# Wise-1510-v1_1_0.net
KiCad netlist of a schematic drawn in EAGLE
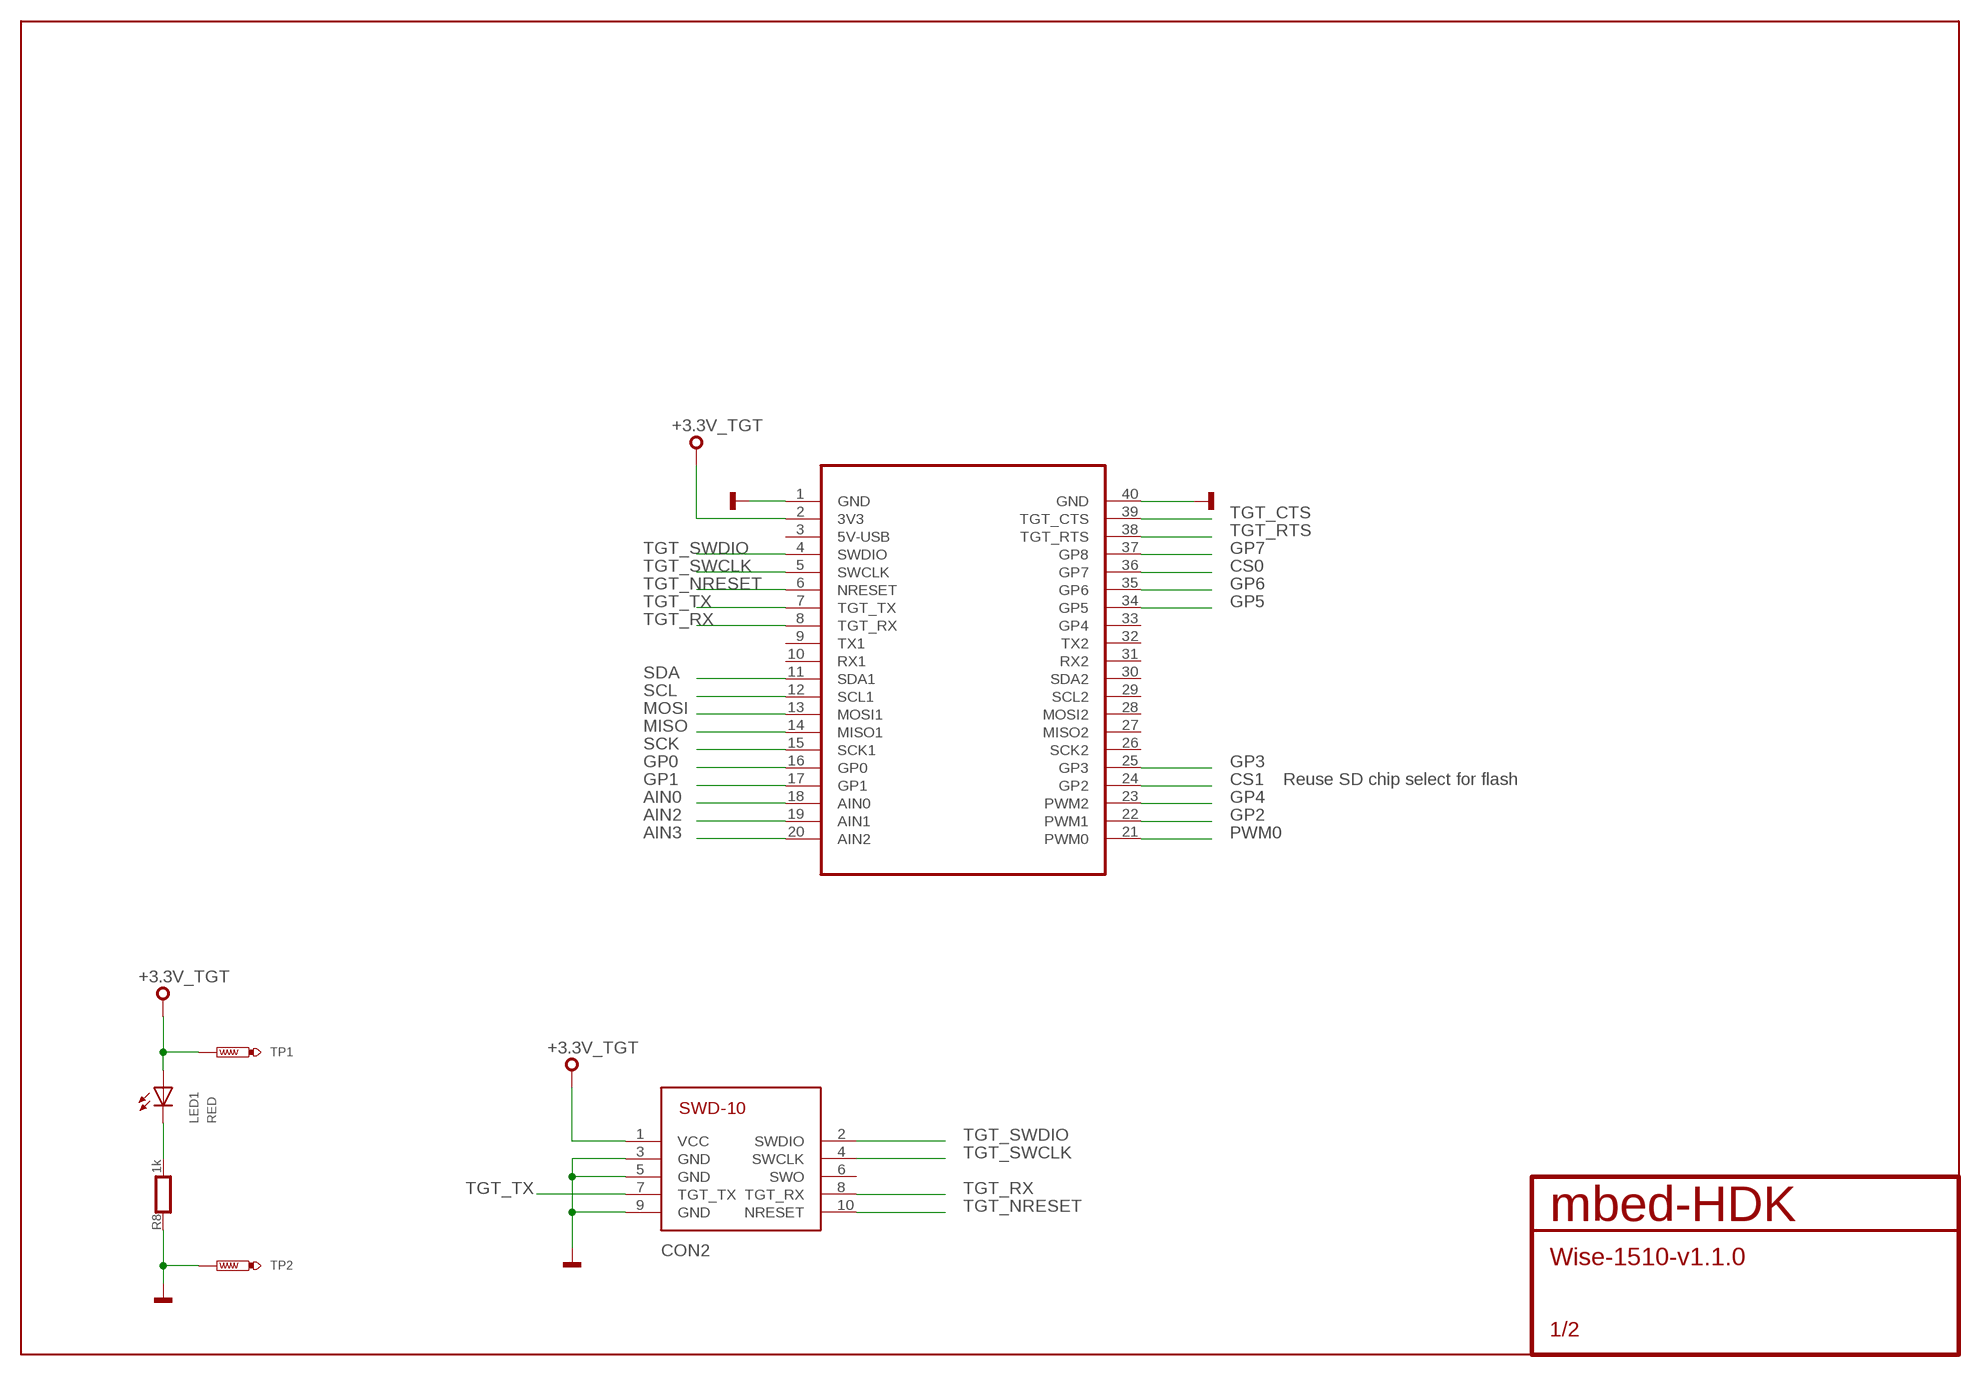
[diagram p0: schematic, sheet 1]
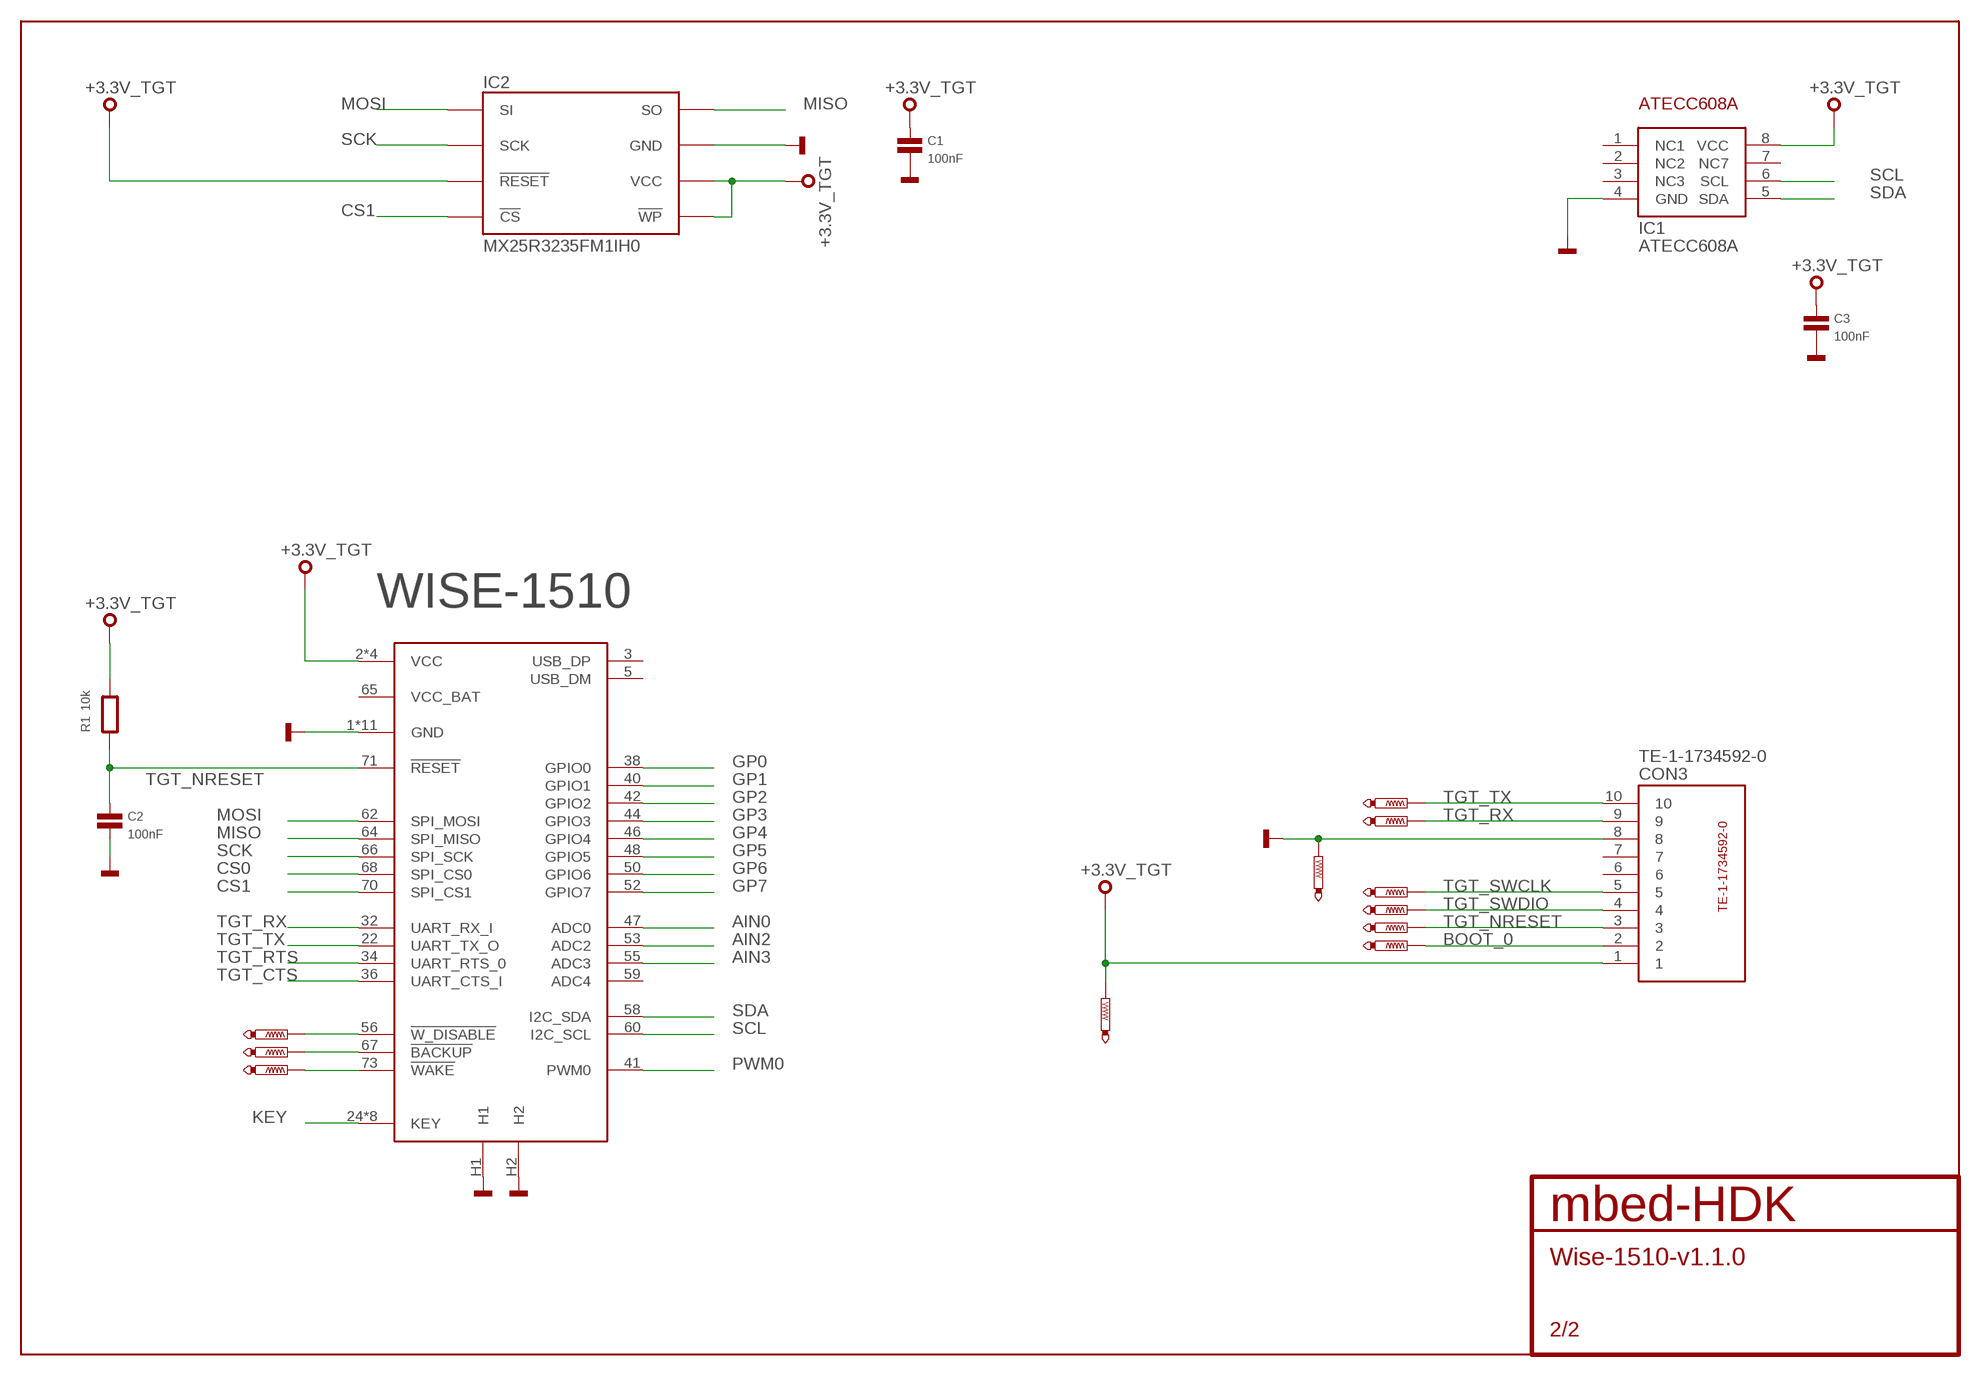
[diagram p1: schematic, sheet 2]

(export (version "E")
  (design (tool "Eeschema 10.0.6"))
  (components
    (comp (ref "C1")
      (value "100nF")
      (footprint "eagle-import:0603")
      (libsource (lib "eagle-import") (part "CAPACITOR0603"))
    )
    (comp (ref "C2")
      (value "100nF")
      (footprint "eagle-import:0603")
      (libsource (lib "eagle-import") (part "CAPACITOR0603"))
    )
    (comp (ref "C3")
      (value "100nF")
      (footprint "eagle-import:0603")
      (libsource (lib "eagle-import") (part "CAPACITOR0603"))
    )
    (comp (ref "CON1")
      (value "WISE-1510_E")
      (footprint "eagle-import:MDT420E02001")
      (libsource (lib "eagle-import") (part "WISE-1510_E"))
    )
    (comp (ref "CON3")
      (value "TE-1-1734592-0")
      (footprint "eagle-import:TE-1-1734592-0")
      (libsource (lib "eagle-import") (part "TE-1-1734592-0"))
    )
    (comp (ref "IC1")
      (value "ATECC608A")
      (footprint "eagle-import:SO8")
      (libsource (lib "eagle-import") (part "ATECC608A"))
    )
    (comp (ref "IC2")
      (value "MX25R3235FM1IH0")
      (footprint "eagle-import:SO8")
      (fields (field (name "MF") "Macronix"))
      (libsource (lib "eagle-import") (part "MX25R3235FM1IH0"))
    )
    (comp (ref "R1")
      (value "10k")
      (footprint "eagle-import:0603")
      (libsource (lib "eagle-import") (part "RESISTOR0603"))
    )
    (comp (ref "TP3")
      (value "PTR1TP08R")
      (footprint "eagle-import:TP08R")
      (libsource (lib "eagle-import") (part "PTR1TP08R"))
    )
    (comp (ref "TP4")
      (value "PTR1TP08R")
      (footprint "eagle-import:TP08R")
      (libsource (lib "eagle-import") (part "PTR1TP08R"))
    )
    (comp (ref "TP5")
      (value "PTR1TP08R")
      (footprint "eagle-import:TP08R")
      (libsource (lib "eagle-import") (part "PTR1TP08R"))
    )
    (comp (ref "TP6")
      (value "PTR1TP08R")
      (footprint "eagle-import:TP08R")
      (libsource (lib "eagle-import") (part "PTR1TP08R"))
    )
    (comp (ref "TP7")
      (value "PTR1TP08R")
      (footprint "eagle-import:TP08R")
      (libsource (lib "eagle-import") (part "PTR1TP08R"))
    )
    (comp (ref "TP8")
      (value "PTR1TP08R")
      (footprint "eagle-import:TP08R")
      (libsource (lib "eagle-import") (part "PTR1TP08R"))
    )
    (comp (ref "TP9")
      (value "PTR1B1,27")
      (footprint "eagle-import:B1,27")
      (libsource (lib "eagle-import") (part "PTR1B1,27"))
    )
    (comp (ref "TP10")
      (value "PTR1B1,27")
      (footprint "eagle-import:B1,27")
      (libsource (lib "eagle-import") (part "PTR1B1,27"))
    )
    (comp (ref "TP11")
      (value "PTR1B1,27")
      (footprint "eagle-import:B1,27")
      (libsource (lib "eagle-import") (part "PTR1B1,27"))
    )
    (comp (ref "TP12")
      (value "PTR1TP08R")
      (footprint "eagle-import:TP08R")
      (libsource (lib "eagle-import") (part "PTR1TP08R"))
    )
    (comp (ref "TP13")
      (value "PTR1TP08R")
      (footprint "eagle-import:TP08R")
      (libsource (lib "eagle-import") (part "PTR1TP08R"))
    )
    (comp (ref "CON2")
      (value "SWD-10/TC2050_SMD")
      (footprint "eagle-import:FTSH-105-02")
      (libsource (lib "eagle-import") (part "SWD-10/TC2050_SMD"))
    )
    (comp (ref "LED1")
      (value "RED")
      (footprint "eagle-import:CHIPLED_0603")
      (fields (field (name "MF") "Wurth Electronics Inc"))
      (libsource (lib "eagle-import") (part "SMD_LED0603"))
    )
    (comp (ref "R8")
      (value "1k")
      (footprint "eagle-import:0603")
      (libsource (lib "eagle-import") (part "RESISTOR0603"))
    )
    (comp (ref "TP1")
      (value "TEST-POINT-50R-PTH")
      (footprint "eagle-import:TP50-PTH")
      (libsource (lib "eagle-import") (part "TEST-POINT-50R-PTH"))
    )
    (comp (ref "TP2")
      (value "TEST-POINT-50R-PTH")
      (footprint "eagle-import:TP50-PTH")
      (libsource (lib "eagle-import") (part "TEST-POINT-50R-PTH"))
    )
    (comp (ref "U$1")
      (value "MODULE_DAUGHTER")
      (footprint "eagle-import:MODULE_DAUGHTER")
      (libsource (lib "eagle-import") (part "MODULE_DAUGHTER"))
    )
  )
  (nets
    (net (code "1") (name "+3.3V_TGT") (class "Default")
      (node (ref "C1") (pin "1") (pinfunction "P$1_1") (pintype "passive"))
      (node (ref "C3") (pin "1") (pinfunction "P$1_1") (pintype "passive"))
      (node (ref "CON1") (pin "2") (pinfunction "VCC_2") (pintype "bidirectional"))
      (node (ref "CON1") (pin "4") (pinfunction "VCC_4") (pintype "bidirectional"))
      (node (ref "CON1") (pin "72") (pinfunction "VCC_72") (pintype "bidirectional"))
      (node (ref "CON1") (pin "74") (pinfunction "VCC_74") (pintype "bidirectional"))
      (node (ref "CON2") (pin "1") (pinfunction "VCC_1") (pintype "bidirectional"))
      (node (ref "CON3") (pin "1") (pinfunction "1_1") (pintype "bidirectional"))
      (node (ref "IC1") (pin "8") (pinfunction "VCC_8") (pintype "bidirectional"))
      (node (ref "IC2") (pin "3") (pinfunction "~{WP}_3") (pintype "bidirectional"))
      (node (ref "IC2") (pin "7") (pinfunction "~{RESET}_7") (pintype "bidirectional"))
      (node (ref "IC2") (pin "8") (pinfunction "VCC_8") (pintype "bidirectional"))
      (node (ref "LED1") (pin "A") (pinfunction "A_A") (pintype "passive"))
      (node (ref "R1") (pin "2") (pinfunction "P$2_2") (pintype "passive"))
      (node (ref "TP1") (pin "TP") (pinfunction "TP_TP") (pintype "input"))
      (node (ref "TP12") (pin "TP") (pinfunction "TP_TP") (pintype "input"))
      (node (ref "U$1") (pin "2") (pinfunction "3V3_2") (pintype "bidirectional"))
    )
    (net (code "2") (name "AIN0") (class "Default")
      (node (ref "CON1") (pin "47") (pinfunction "ADC0_47") (pintype "bidirectional"))
      (node (ref "U$1") (pin "18") (pinfunction "AIN0_18") (pintype "bidirectional"))
    )
    (net (code "3") (name "AIN2") (class "Default")
      (node (ref "CON1") (pin "53") (pinfunction "ADC2_53") (pintype "bidirectional"))
      (node (ref "U$1") (pin "19") (pinfunction "AIN1_19") (pintype "bidirectional"))
    )
    (net (code "4") (name "AIN3") (class "Default")
      (node (ref "CON1") (pin "55") (pinfunction "ADC3_55") (pintype "bidirectional"))
      (node (ref "U$1") (pin "20") (pinfunction "AIN2_20") (pintype "bidirectional"))
    )
    (net (code "5") (name "BOOT_0") (class "Default")
      (node (ref "CON3") (pin "2") (pinfunction "2_2") (pintype "bidirectional"))
      (node (ref "TP8") (pin "TP") (pinfunction "TP_TP") (pintype "input"))
    )
    (net (code "6") (name "CS0") (class "Default")
      (node (ref "CON1") (pin "68") (pinfunction "SPI_CS0_68") (pintype "bidirectional"))
      (node (ref "U$1") (pin "36") (pinfunction "GP7_36") (pintype "bidirectional"))
    )
    (net (code "7") (name "CS1") (class "Default")
      (node (ref "CON1") (pin "70") (pinfunction "SPI_CS1_70") (pintype "bidirectional"))
      (node (ref "IC2") (pin "1") (pinfunction "~{CS}_1") (pintype "bidirectional"))
      (node (ref "U$1") (pin "24") (pinfunction "GP2_24") (pintype "bidirectional"))
    )
    (net (code "8") (name "GND") (class "Default")
      (node (ref "C1") (pin "2") (pinfunction "P$2_2") (pintype "passive"))
      (node (ref "C2") (pin "2") (pinfunction "P$2_2") (pintype "passive"))
      (node (ref "C3") (pin "2") (pinfunction "P$2_2") (pintype "passive"))
      (node (ref "CON1") (pin "1") (pinfunction "GND_1") (pintype "bidirectional"))
      (node (ref "CON1") (pin "18") (pinfunction "GND_18") (pintype "bidirectional"))
      (node (ref "CON1") (pin "33") (pinfunction "GND_33") (pintype "bidirectional"))
      (node (ref "CON1") (pin "39") (pinfunction "GND_39") (pintype "bidirectional"))
      (node (ref "CON1") (pin "45") (pinfunction "GND_45") (pintype "bidirectional"))
      (node (ref "CON1") (pin "51") (pinfunction "GND_51") (pintype "bidirectional"))
      (node (ref "CON1") (pin "57") (pinfunction "GND_57") (pintype "bidirectional"))
      (node (ref "CON1") (pin "63") (pinfunction "GND_63") (pintype "bidirectional"))
      (node (ref "CON1") (pin "69") (pinfunction "GND_69") (pintype "bidirectional"))
      (node (ref "CON1") (pin "7") (pinfunction "GND_7") (pintype "bidirectional"))
      (node (ref "CON1") (pin "75") (pinfunction "GND_75") (pintype "bidirectional"))
      (node (ref "CON1") (pin "H1") (pinfunction "H1_H1") (pintype "bidirectional"))
      (node (ref "CON1") (pin "H2") (pinfunction "H2_H2") (pintype "bidirectional"))
      (node (ref "CON2") (pin "3") (pinfunction "GND_3") (pintype "bidirectional"))
      (node (ref "CON2") (pin "5") (pinfunction "GND_5") (pintype "bidirectional"))
      (node (ref "CON2") (pin "9") (pinfunction "GND_9") (pintype "bidirectional"))
      (node (ref "CON3") (pin "8") (pinfunction "8_8") (pintype "bidirectional"))
      (node (ref "IC1") (pin "4") (pinfunction "GND_4") (pintype "bidirectional"))
      (node (ref "IC2") (pin "4") (pinfunction "GND_4") (pintype "bidirectional"))
      (node (ref "R8") (pin "1") (pinfunction "P$1_1") (pintype "passive"))
      (node (ref "TP13") (pin "TP") (pinfunction "TP_TP") (pintype "input"))
      (node (ref "TP2") (pin "TP") (pinfunction "TP_TP") (pintype "input"))
      (node (ref "U$1") (pin "1") (pinfunction "GND_1") (pintype "bidirectional"))
      (node (ref "U$1") (pin "40") (pinfunction "GND_40") (pintype "bidirectional"))
    )
    (net (code "9") (name "GP0") (class "Default")
      (node (ref "CON1") (pin "38") (pinfunction "GPIO0_38") (pintype "bidirectional"))
      (node (ref "U$1") (pin "16") (pinfunction "GP0_16") (pintype "bidirectional"))
    )
    (net (code "10") (name "GP1") (class "Default")
      (node (ref "CON1") (pin "40") (pinfunction "GPIO1_40") (pintype "bidirectional"))
      (node (ref "U$1") (pin "17") (pinfunction "GP1_17") (pintype "bidirectional"))
    )
    (net (code "11") (name "GP2") (class "Default")
      (node (ref "CON1") (pin "42") (pinfunction "GPIO2_42") (pintype "bidirectional"))
      (node (ref "U$1") (pin "22") (pinfunction "PWM1_22") (pintype "bidirectional"))
    )
    (net (code "12") (name "GP3") (class "Default")
      (node (ref "CON1") (pin "44") (pinfunction "GPIO3_44") (pintype "bidirectional"))
      (node (ref "U$1") (pin "25") (pinfunction "GP3_25") (pintype "bidirectional"))
    )
    (net (code "13") (name "GP4") (class "Default")
      (node (ref "CON1") (pin "46") (pinfunction "GPIO4_46") (pintype "bidirectional"))
      (node (ref "U$1") (pin "23") (pinfunction "PWM2_23") (pintype "bidirectional"))
    )
    (net (code "14") (name "GP5") (class "Default")
      (node (ref "CON1") (pin "48") (pinfunction "GPIO5_48") (pintype "bidirectional"))
      (node (ref "U$1") (pin "34") (pinfunction "GP5_34") (pintype "bidirectional"))
    )
    (net (code "15") (name "GP6") (class "Default")
      (node (ref "CON1") (pin "50") (pinfunction "GPIO6_50") (pintype "bidirectional"))
      (node (ref "U$1") (pin "35") (pinfunction "GP6_35") (pintype "bidirectional"))
    )
    (net (code "16") (name "GP7") (class "Default")
      (node (ref "CON1") (pin "52") (pinfunction "GPIO7_52") (pintype "bidirectional"))
      (node (ref "U$1") (pin "37") (pinfunction "GP8_37") (pintype "bidirectional"))
    )
    (net (code "17") (name "KEY") (class "Default")
      (node (ref "CON1") (pin "24") (pinfunction "KEY_24") (pintype "bidirectional"))
      (node (ref "CON1") (pin "25") (pinfunction "KEY_25") (pintype "bidirectional"))
      (node (ref "CON1") (pin "26") (pinfunction "KEY_26") (pintype "bidirectional"))
      (node (ref "CON1") (pin "27") (pinfunction "KEY_27") (pintype "bidirectional"))
      (node (ref "CON1") (pin "28") (pinfunction "KEY_28") (pintype "bidirectional"))
      (node (ref "CON1") (pin "29") (pinfunction "KEY_29") (pintype "bidirectional"))
      (node (ref "CON1") (pin "30") (pinfunction "KEY_30") (pintype "bidirectional"))
      (node (ref "CON1") (pin "31") (pinfunction "KEY_31") (pintype "bidirectional"))
    )
    (net (code "18") (name "MISO") (class "Default")
      (node (ref "CON1") (pin "64") (pinfunction "SPI_MISO_64") (pintype "bidirectional"))
      (node (ref "IC2") (pin "2") (pinfunction "SO_2") (pintype "bidirectional"))
      (node (ref "U$1") (pin "14") (pinfunction "MISO1_14") (pintype "bidirectional"))
    )
    (net (code "19") (name "MOSI") (class "Default")
      (node (ref "CON1") (pin "62") (pinfunction "SPI_MOSI_62") (pintype "bidirectional"))
      (node (ref "IC2") (pin "5") (pinfunction "SI_5") (pintype "bidirectional"))
      (node (ref "U$1") (pin "13") (pinfunction "MOSI1_13") (pintype "bidirectional"))
    )
    (net (code "20") (name "Net-(CON1-~{BACKUP})") (class "Default")
      (node (ref "CON1") (pin "67") (pinfunction "~{BACKUP}_67") (pintype "bidirectional"))
      (node (ref "TP10") (pin "TP") (pinfunction "TP_TP") (pintype "input"))
    )
    (net (code "21") (name "Net-(CON1-~{WAKE})") (class "Default")
      (node (ref "CON1") (pin "73") (pinfunction "~{WAKE}_73") (pintype "bidirectional"))
      (node (ref "TP11") (pin "TP") (pinfunction "TP_TP") (pintype "input"))
    )
    (net (code "22") (name "Net-(CON1-~{W_DISABLE})") (class "Default")
      (node (ref "CON1") (pin "56") (pinfunction "~{W_DISABLE}_56") (pintype "bidirectional"))
      (node (ref "TP9") (pin "TP") (pinfunction "TP_TP") (pintype "input"))
    )
    (net (code "23") (name "Net-(R8-P$2)") (class "Default")
      (node (ref "LED1") (pin "C") (pinfunction "C_C") (pintype "passive"))
      (node (ref "R8") (pin "2") (pinfunction "P$2_2") (pintype "passive"))
    )
    (net (code "24") (name "PWM0") (class "Default")
      (node (ref "CON1") (pin "41") (pinfunction "PWM0_41") (pintype "bidirectional"))
      (node (ref "U$1") (pin "21") (pinfunction "PWM0_21") (pintype "bidirectional"))
    )
    (net (code "25") (name "SCK") (class "Default")
      (node (ref "CON1") (pin "66") (pinfunction "SPI_SCK_66") (pintype "bidirectional"))
      (node (ref "IC2") (pin "6") (pinfunction "SCK_6") (pintype "bidirectional"))
      (node (ref "U$1") (pin "15") (pinfunction "SCK1_15") (pintype "bidirectional"))
    )
    (net (code "26") (name "SCL") (class "Default")
      (node (ref "CON1") (pin "60") (pinfunction "I2C_SCL_60") (pintype "bidirectional"))
      (node (ref "IC1") (pin "6") (pinfunction "SCL_6") (pintype "bidirectional"))
      (node (ref "U$1") (pin "12") (pinfunction "SCL1_12") (pintype "bidirectional"))
    )
    (net (code "27") (name "SDA") (class "Default")
      (node (ref "CON1") (pin "58") (pinfunction "I2C_SDA_58") (pintype "bidirectional"))
      (node (ref "IC1") (pin "5") (pinfunction "SDA_5") (pintype "bidirectional"))
      (node (ref "U$1") (pin "11") (pinfunction "SDA1_11") (pintype "bidirectional"))
    )
    (net (code "28") (name "TGT_CTS") (class "Default")
      (node (ref "CON1") (pin "36") (pinfunction "UART_CTS_I_36") (pintype "bidirectional"))
      (node (ref "U$1") (pin "39") (pinfunction "TGT_CTS_39") (pintype "bidirectional"))
    )
    (net (code "29") (name "TGT_NRESET") (class "Default")
      (node (ref "C2") (pin "1") (pinfunction "P$1_1") (pintype "passive"))
      (node (ref "CON1") (pin "71") (pinfunction "~{RESET}_71") (pintype "bidirectional"))
      (node (ref "CON2") (pin "10") (pinfunction "NRESET_10") (pintype "bidirectional"))
      (node (ref "CON3") (pin "3") (pinfunction "3_3") (pintype "bidirectional"))
      (node (ref "R1") (pin "1") (pinfunction "P$1_1") (pintype "passive"))
      (node (ref "TP5") (pin "TP") (pinfunction "TP_TP") (pintype "input"))
      (node (ref "U$1") (pin "6") (pinfunction "NRESET_6") (pintype "bidirectional"))
    )
    (net (code "30") (name "TGT_RTS") (class "Default")
      (node (ref "CON1") (pin "34") (pinfunction "UART_RTS_0_34") (pintype "bidirectional"))
      (node (ref "U$1") (pin "38") (pinfunction "TGT_RTS_38") (pintype "bidirectional"))
    )
    (net (code "31") (name "TGT_RX") (class "Default")
      (node (ref "CON1") (pin "32") (pinfunction "UART_RX_I_32") (pintype "bidirectional"))
      (node (ref "CON2") (pin "8") (pinfunction "TGT_RX_8") (pintype "bidirectional"))
      (node (ref "CON3") (pin "9") (pinfunction "9_9") (pintype "bidirectional"))
      (node (ref "TP6") (pin "TP") (pinfunction "TP_TP") (pintype "input"))
      (node (ref "U$1") (pin "8") (pinfunction "TGT_RX_8") (pintype "bidirectional"))
    )
    (net (code "32") (name "TGT_SWCLK") (class "Default")
      (node (ref "CON2") (pin "4") (pinfunction "SWCLK_4") (pintype "bidirectional"))
      (node (ref "CON3") (pin "5") (pinfunction "5_5") (pintype "bidirectional"))
      (node (ref "TP3") (pin "TP") (pinfunction "TP_TP") (pintype "input"))
      (node (ref "U$1") (pin "5") (pinfunction "SWCLK_5") (pintype "bidirectional"))
    )
    (net (code "33") (name "TGT_SWDIO") (class "Default")
      (node (ref "CON2") (pin "2") (pinfunction "SWDIO_2") (pintype "bidirectional"))
      (node (ref "CON3") (pin "4") (pinfunction "4_4") (pintype "bidirectional"))
      (node (ref "TP4") (pin "TP") (pinfunction "TP_TP") (pintype "input"))
      (node (ref "U$1") (pin "4") (pinfunction "SWDIO_4") (pintype "bidirectional"))
    )
    (net (code "34") (name "TGT_TX") (class "Default")
      (node (ref "CON1") (pin "22") (pinfunction "UART_TX_O_22") (pintype "bidirectional"))
      (node (ref "CON2") (pin "7") (pinfunction "TGT_TX_7") (pintype "bidirectional"))
      (node (ref "CON3") (pin "10") (pinfunction "10_10") (pintype "bidirectional"))
      (node (ref "TP7") (pin "TP") (pinfunction "TP_TP") (pintype "input"))
      (node (ref "U$1") (pin "7") (pinfunction "TGT_TX_7") (pintype "bidirectional"))
    )
    (net (code "35") (name "unconnected-(CON1-ADC4-Pad59)") (class "Default")
      (node (ref "CON1") (pin "59") (pinfunction "ADC4_59") (pintype "bidirectional"))
    )
    (net (code "36") (name "unconnected-(CON1-USB_DM-Pad5)") (class "Default")
      (node (ref "CON1") (pin "5") (pinfunction "USB_DM_5") (pintype "bidirectional"))
    )
    (net (code "37") (name "unconnected-(CON1-USB_DP-Pad3)") (class "Default")
      (node (ref "CON1") (pin "3") (pinfunction "USB_DP_3") (pintype "bidirectional"))
    )
    (net (code "38") (name "unconnected-(CON1-VCC_BAT-Pad65)") (class "Default")
      (node (ref "CON1") (pin "65") (pinfunction "VCC_BAT_65") (pintype "bidirectional"))
    )
    (net (code "39") (name "unconnected-(CON2-SWO-Pad6)") (class "Default")
      (node (ref "CON2") (pin "6") (pinfunction "SWO_6") (pintype "bidirectional"))
    )
    (net (code "40") (name "unconnected-(CON3-Pad6)") (class "Default")
      (node (ref "CON3") (pin "6") (pinfunction "6_6") (pintype "bidirectional"))
    )
    (net (code "41") (name "unconnected-(CON3-Pad7)") (class "Default")
      (node (ref "CON3") (pin "7") (pinfunction "7_7") (pintype "bidirectional"))
    )
    (net (code "42") (name "unconnected-(IC1-NC1-Pad1)") (class "Default")
      (node (ref "IC1") (pin "1") (pinfunction "NC1_1") (pintype "bidirectional"))
    )
    (net (code "43") (name "unconnected-(IC1-NC2-Pad2)") (class "Default")
      (node (ref "IC1") (pin "2") (pinfunction "NC2_2") (pintype "bidirectional"))
    )
    (net (code "44") (name "unconnected-(IC1-NC3-Pad3)") (class "Default")
      (node (ref "IC1") (pin "3") (pinfunction "NC3_3") (pintype "bidirectional"))
    )
    (net (code "45") (name "unconnected-(IC1-NC7-Pad7)") (class "Default")
      (node (ref "IC1") (pin "7") (pinfunction "NC7_7") (pintype "bidirectional"))
    )
    (net (code "46") (name "unconnected-(U$1-5V-USB-Pad3)") (class "Default")
      (node (ref "U$1") (pin "3") (pinfunction "5V-USB_3") (pintype "bidirectional"))
    )
    (net (code "47") (name "unconnected-(U$1-GP4-Pad33)") (class "Default")
      (node (ref "U$1") (pin "33") (pinfunction "GP4_33") (pintype "bidirectional"))
    )
    (net (code "48") (name "unconnected-(U$1-MISO2-Pad27)") (class "Default")
      (node (ref "U$1") (pin "27") (pinfunction "MISO2_27") (pintype "bidirectional"))
    )
    (net (code "49") (name "unconnected-(U$1-MOSI2-Pad28)") (class "Default")
      (node (ref "U$1") (pin "28") (pinfunction "MOSI2_28") (pintype "bidirectional"))
    )
    (net (code "50") (name "unconnected-(U$1-RX1-Pad10)") (class "Default")
      (node (ref "U$1") (pin "10") (pinfunction "RX1_10") (pintype "bidirectional"))
    )
    (net (code "51") (name "unconnected-(U$1-RX2-Pad31)") (class "Default")
      (node (ref "U$1") (pin "31") (pinfunction "RX2_31") (pintype "bidirectional"))
    )
    (net (code "52") (name "unconnected-(U$1-SCK2-Pad26)") (class "Default")
      (node (ref "U$1") (pin "26") (pinfunction "SCK2_26") (pintype "bidirectional"))
    )
    (net (code "53") (name "unconnected-(U$1-SCL2-Pad29)") (class "Default")
      (node (ref "U$1") (pin "29") (pinfunction "SCL2_29") (pintype "bidirectional"))
    )
    (net (code "54") (name "unconnected-(U$1-SDA2-Pad30)") (class "Default")
      (node (ref "U$1") (pin "30") (pinfunction "SDA2_30") (pintype "bidirectional"))
    )
    (net (code "55") (name "unconnected-(U$1-TX1-Pad9)") (class "Default")
      (node (ref "U$1") (pin "9") (pinfunction "TX1_9") (pintype "bidirectional"))
    )
    (net (code "56") (name "unconnected-(U$1-TX2-Pad32)") (class "Default")
      (node (ref "U$1") (pin "32") (pinfunction "TX2_32") (pintype "bidirectional"))
    )
  )
)
